# alphanewt_v1_8.net
KiCad netlist of a schematic drawn in EAGLE
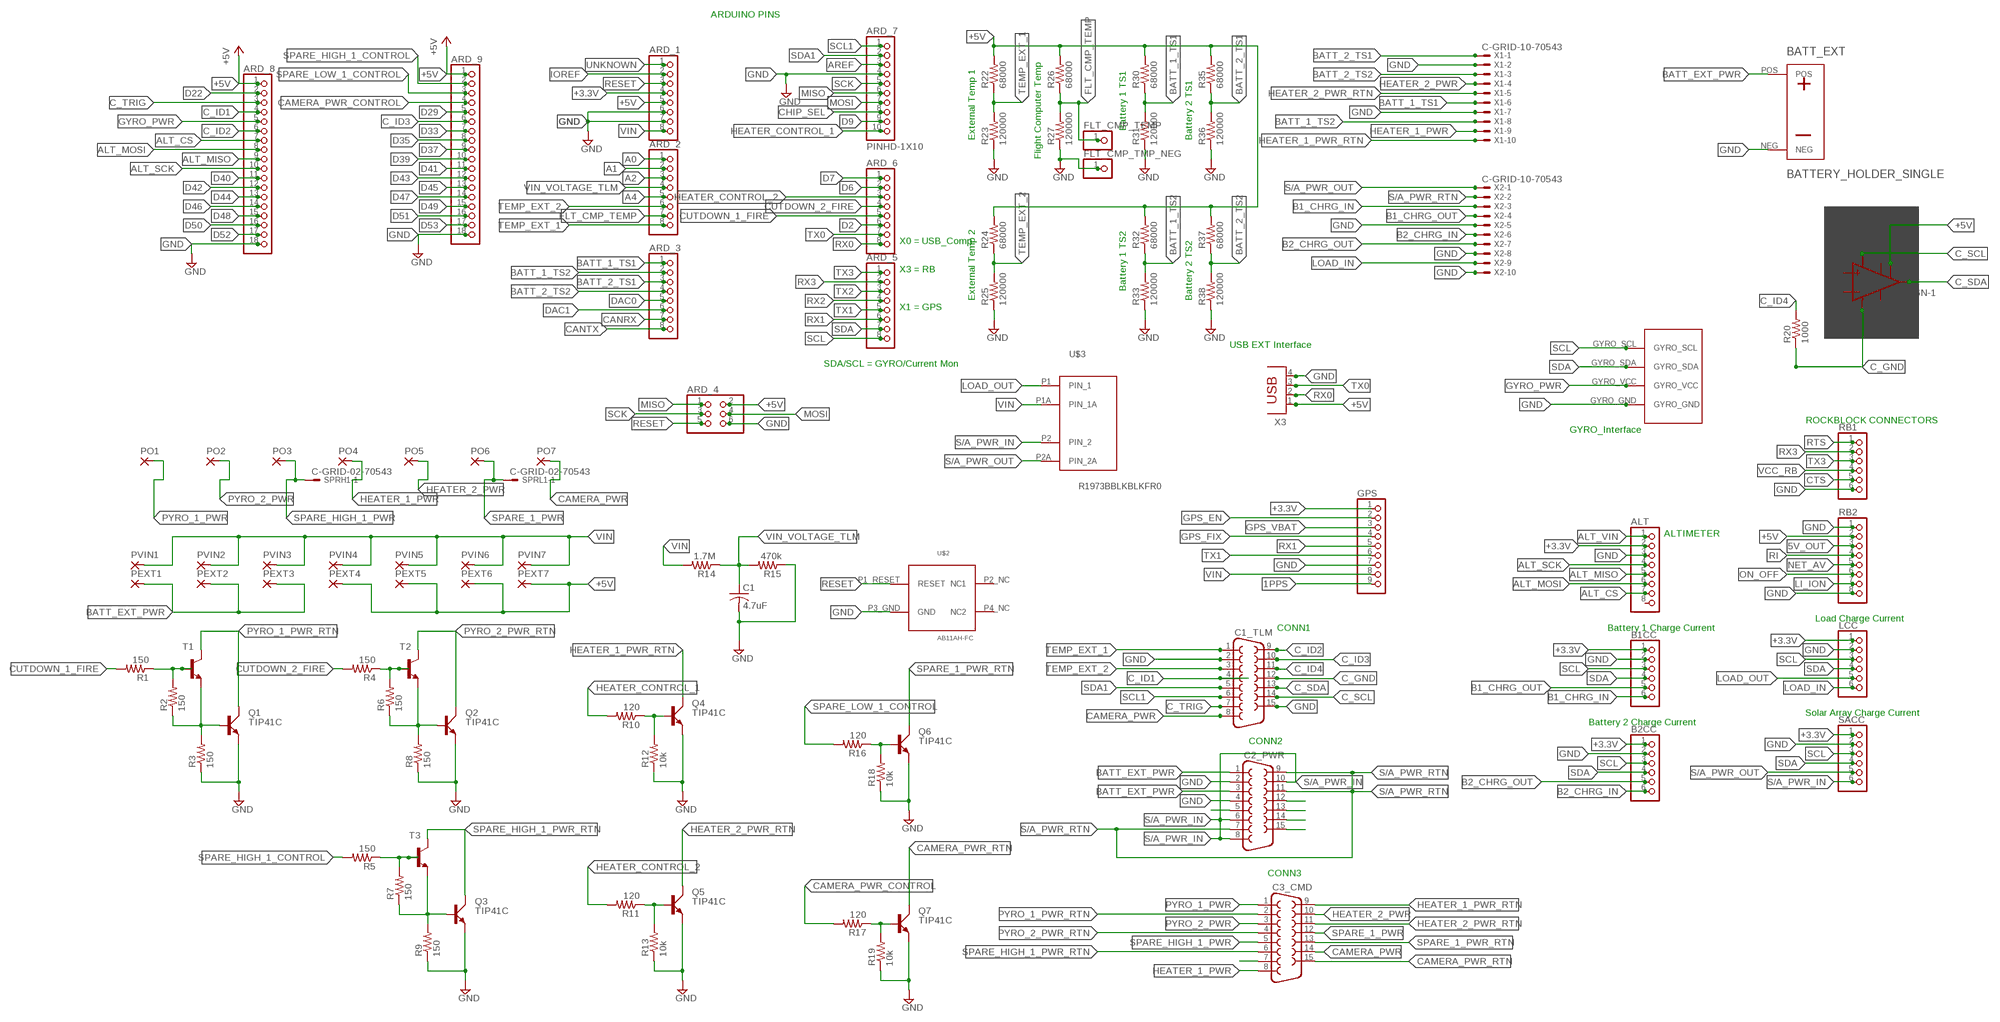
[diagram p0: schematic, sheet 1]

(export (version "E")
  (design (tool "Eeschema 10.0.6"))
  (components
    (comp (ref "ALT")
      (value "PINHD-1X8BIG")
      (footprint "eagle-import:1X08-BIG")
      (libsource (lib "eagle-import") (part "PINHD-1X8BIG"))
    )
    (comp (ref "ARD_1")
      (value "PINHD-1X8BIG")
      (footprint "eagle-import:1X08-BIG")
      (libsource (lib "eagle-import") (part "PINHD-1X8BIG"))
    )
    (comp (ref "ARD_2")
      (value "PINHD-1X8BIG")
      (footprint "eagle-import:1X08-BIG")
      (libsource (lib "eagle-import") (part "PINHD-1X8BIG"))
    )
    (comp (ref "ARD_3")
      (value "PINHD-1X8BIG")
      (footprint "eagle-import:1X08-BIG")
      (libsource (lib "eagle-import") (part "PINHD-1X8BIG"))
    )
    (comp (ref "ARD_4")
      (value "PINHD-2X3")
      (footprint "eagle-import:2X03")
      (libsource (lib "eagle-import") (part "PINHD-2X3"))
    )
    (comp (ref "ARD_5")
      (value "PINHD-1X8BIG")
      (footprint "eagle-import:1X08-BIG")
      (libsource (lib "eagle-import") (part "PINHD-1X8BIG"))
    )
    (comp (ref "ARD_6")
      (value "PINHD-1X8BIG")
      (footprint "eagle-import:1X08-BIG")
      (libsource (lib "eagle-import") (part "PINHD-1X8BIG"))
    )
    (comp (ref "ARD_7")
      (value "PINHD-1X10")
      (footprint "eagle-import:1X10-BIG")
      (libsource (lib "eagle-import") (part "PINHD-1X10"))
    )
    (comp (ref "ARD_8")
      (value "PINHD-1X18-BIG")
      (footprint "eagle-import:1X18-BIG")
      (libsource (lib "eagle-import") (part "PINHD-1X18-BIG"))
    )
    (comp (ref "ARD_9")
      (value "PINHD-1X18-BIG")
      (footprint "eagle-import:1X18-BIG")
      (libsource (lib "eagle-import") (part "PINHD-1X18-BIG"))
    )
    (comp (ref "B1CC")
      (value "PINHD-1X6B")
      (footprint "eagle-import:1X06-BIG")
      (libsource (lib "eagle-import") (part "PINHD-1X6B"))
    )
    (comp (ref "B2CC")
      (value "PINHD-1X6B")
      (footprint "eagle-import:1X06-BIG")
      (libsource (lib "eagle-import") (part "PINHD-1X6B"))
    )
    (comp (ref "BATT_EXT")
      (value "BATTERY_HOLDER_SINGLE")
      (footprint "eagle-import:BATT_HOLDER_SINGLE")
      (libsource (lib "eagle-import") (part "BATTERY_HOLDER_SINGLE"))
    )
    (comp (ref "C1")
      (value "4.7uF")
      (footprint "eagle-import:C0805K")
      (fields (field (name "MPN") "C2012X6S1H475K125AC"))
      (libsource (lib "eagle-import") (part "C-USC0805K"))
    )
    (comp (ref "C1_TLM")
      (value "F15HP")
      (footprint "eagle-import:F15HP")
      (fields (field (name "MPN") "5504F1-15S-02A-03"))
      (libsource (lib "eagle-import") (part "F15HP"))
    )
    (comp (ref "C2_PWR")
      (value "F15HP")
      (footprint "eagle-import:F15HP")
      (fields (field (name "MPN") "5504F1-15S-02A-03"))
      (libsource (lib "eagle-import") (part "F15HP"))
    )
    (comp (ref "C3_CMD")
      (value "F15HP")
      (footprint "eagle-import:F15HP")
      (fields (field (name "MPN") "5504F1-15S-02A-03"))
      (libsource (lib "eagle-import") (part "F15HP"))
    )
    (comp (ref "FLT_CMP_TEMP")
      (value "PINHD-1X1")
      (footprint "eagle-import:1X01")
      (libsource (lib "eagle-import") (part "PINHD-1X1"))
    )
    (comp (ref "FLT_CMP_TMP_NEG")
      (value "PINHD-1X1")
      (footprint "eagle-import:1X01")
      (libsource (lib "eagle-import") (part "PINHD-1X1"))
    )
    (comp (ref "GPS")
      (value "PINHD-1X9")
      (footprint "eagle-import:1X09-BIG")
      (libsource (lib "eagle-import") (part "PINHD-1X9"))
    )
    (comp (ref "IC1")
      (value "LM386N-1")
      (footprint "eagle-import:DIL08")
      (libsource (lib "eagle-import") (part "LM386?-N1"))
    )
    (comp (ref "LCC")
      (value "PINHD-1X6B")
      (footprint "eagle-import:1X06-BIG")
      (libsource (lib "eagle-import") (part "PINHD-1X6B"))
    )
    (comp (ref "PEXT1")
      (value "SMD2")
      (footprint "eagle-import:SMD1,27-2,54")
      (libsource (lib "eagle-import") (part "SMD2"))
    )
    (comp (ref "PEXT2")
      (value "SMD2")
      (footprint "eagle-import:SMD1,27-2,54")
      (libsource (lib "eagle-import") (part "SMD2"))
    )
    (comp (ref "PEXT3")
      (value "SMD2")
      (footprint "eagle-import:SMD1,27-2,54")
      (libsource (lib "eagle-import") (part "SMD2"))
    )
    (comp (ref "PEXT4")
      (value "SMD2")
      (footprint "eagle-import:SMD1,27-2,54")
      (libsource (lib "eagle-import") (part "SMD2"))
    )
    (comp (ref "PEXT5")
      (value "SMD2")
      (footprint "eagle-import:SMD1,27-2,54")
      (libsource (lib "eagle-import") (part "SMD2"))
    )
    (comp (ref "PEXT6")
      (value "SMD2")
      (footprint "eagle-import:SMD1,27-2,54")
      (libsource (lib "eagle-import") (part "SMD2"))
    )
    (comp (ref "PEXT7")
      (value "SMD2")
      (footprint "eagle-import:SMD1,27-2,54")
      (libsource (lib "eagle-import") (part "SMD2"))
    )
    (comp (ref "PO1")
      (value "SMD2")
      (footprint "eagle-import:SMD1,27-2,54")
      (libsource (lib "eagle-import") (part "SMD2"))
    )
    (comp (ref "PO2")
      (value "SMD2")
      (footprint "eagle-import:SMD1,27-2,54")
      (libsource (lib "eagle-import") (part "SMD2"))
    )
    (comp (ref "PO3")
      (value "SMD2")
      (footprint "eagle-import:SMD1,27-2,54")
      (libsource (lib "eagle-import") (part "SMD2"))
    )
    (comp (ref "PO4")
      (value "SMD2")
      (footprint "eagle-import:SMD1,27-2,54")
      (libsource (lib "eagle-import") (part "SMD2"))
    )
    (comp (ref "PO5")
      (value "SMD2")
      (footprint "eagle-import:SMD1,27-2,54")
      (libsource (lib "eagle-import") (part "SMD2"))
    )
    (comp (ref "PO6")
      (value "SMD2")
      (footprint "eagle-import:SMD1,27-2,54")
      (libsource (lib "eagle-import") (part "SMD2"))
    )
    (comp (ref "PO7")
      (value "SMD2")
      (footprint "eagle-import:SMD1,27-2,54")
      (libsource (lib "eagle-import") (part "SMD2"))
    )
    (comp (ref "PVIN1")
      (value "SMD2")
      (footprint "eagle-import:SMD1,27-2,54")
      (libsource (lib "eagle-import") (part "SMD2"))
    )
    (comp (ref "PVIN2")
      (value "SMD2")
      (footprint "eagle-import:SMD1,27-2,54")
      (libsource (lib "eagle-import") (part "SMD2"))
    )
    (comp (ref "PVIN3")
      (value "SMD2")
      (footprint "eagle-import:SMD1,27-2,54")
      (libsource (lib "eagle-import") (part "SMD2"))
    )
    (comp (ref "PVIN4")
      (value "SMD2")
      (footprint "eagle-import:SMD1,27-2,54")
      (libsource (lib "eagle-import") (part "SMD2"))
    )
    (comp (ref "PVIN5")
      (value "SMD2")
      (footprint "eagle-import:SMD1,27-2,54")
      (libsource (lib "eagle-import") (part "SMD2"))
    )
    (comp (ref "PVIN6")
      (value "SMD2")
      (footprint "eagle-import:SMD1,27-2,54")
      (libsource (lib "eagle-import") (part "SMD2"))
    )
    (comp (ref "PVIN7")
      (value "SMD2")
      (footprint "eagle-import:SMD1,27-2,54")
      (libsource (lib "eagle-import") (part "SMD2"))
    )
    (comp (ref "Q1")
      (value "TIP41C")
      (footprint "eagle-import:TO220AV")
      (fields (field (name "MF") "FAIRCHILD SEMICONDUCTOR"))
      (libsource (lib "eagle-import") (part "TIP41C"))
    )
    (comp (ref "Q2")
      (value "TIP41C")
      (footprint "eagle-import:TO220AV")
      (fields (field (name "MF") "FAIRCHILD SEMICONDUCTOR"))
      (libsource (lib "eagle-import") (part "TIP41C"))
    )
    (comp (ref "Q3")
      (value "TIP41C")
      (footprint "eagle-import:TO220AV")
      (fields (field (name "MF") "FAIRCHILD SEMICONDUCTOR"))
      (libsource (lib "eagle-import") (part "TIP41C"))
    )
    (comp (ref "Q4")
      (value "TIP41C")
      (footprint "eagle-import:TO220AV")
      (fields (field (name "MF") "FAIRCHILD SEMICONDUCTOR"))
      (libsource (lib "eagle-import") (part "TIP41C"))
    )
    (comp (ref "Q5")
      (value "TIP41C")
      (footprint "eagle-import:TO220AV")
      (fields (field (name "MF") "FAIRCHILD SEMICONDUCTOR"))
      (libsource (lib "eagle-import") (part "TIP41C"))
    )
    (comp (ref "Q6")
      (value "TIP41C")
      (footprint "eagle-import:TO220AV")
      (fields (field (name "MF") "FAIRCHILD SEMICONDUCTOR"))
      (libsource (lib "eagle-import") (part "TIP41C"))
    )
    (comp (ref "Q7")
      (value "TIP41C")
      (footprint "eagle-import:TO220AV")
      (fields (field (name "MF") "FAIRCHILD SEMICONDUCTOR"))
      (libsource (lib "eagle-import") (part "TIP41C"))
    )
    (comp (ref "R1")
      (value "150")
      (footprint "eagle-import:R0805")
      (fields (field (name "MF") "VISHAY/DALE") (field (name "MPN") "CRCW120633R2FKEA"))
      (libsource (lib "eagle-import") (part "R-US_R0805"))
    )
    (comp (ref "R2")
      (value "150")
      (footprint "eagle-import:R0805")
      (fields (field (name "MF") "VISHAY/DALE") (field (name "MPN") "CRCW120633R2FKEA"))
      (libsource (lib "eagle-import") (part "R-US_R0805"))
    )
    (comp (ref "R3")
      (value "150")
      (footprint "eagle-import:R0805")
      (fields (field (name "MF") "VISHAY/DALE") (field (name "MPN") "CRCW120633R2FKEA"))
      (libsource (lib "eagle-import") (part "R-US_R0805"))
    )
    (comp (ref "R4")
      (value "150")
      (footprint "eagle-import:R0805")
      (fields (field (name "MF") "VISHAY/DALE") (field (name "MPN") "CRCW120633R2FKEA"))
      (libsource (lib "eagle-import") (part "R-US_R0805"))
    )
    (comp (ref "R5")
      (value "150")
      (footprint "eagle-import:R0805")
      (fields (field (name "MF") "VISHAY/DALE") (field (name "MPN") "CRCW120633R2FKEA"))
      (libsource (lib "eagle-import") (part "R-US_R0805"))
    )
    (comp (ref "R6")
      (value "150")
      (footprint "eagle-import:R0805")
      (fields (field (name "MF") "VISHAY/DALE") (field (name "MPN") "CRCW120633R2FKEA"))
      (libsource (lib "eagle-import") (part "R-US_R0805"))
    )
    (comp (ref "R7")
      (value "150")
      (footprint "eagle-import:R0805")
      (fields (field (name "MF") "VISHAY/DALE") (field (name "MPN") "CRCW120633R2FKEA"))
      (libsource (lib "eagle-import") (part "R-US_R0805"))
    )
    (comp (ref "R8")
      (value "150")
      (footprint "eagle-import:R0805")
      (fields (field (name "MF") "VISHAY/DALE") (field (name "MPN") "CRCW120633R2FKEA"))
      (libsource (lib "eagle-import") (part "R-US_R0805"))
    )
    (comp (ref "R9")
      (value "150")
      (footprint "eagle-import:R0805")
      (fields (field (name "MF") "VISHAY/DALE") (field (name "MPN") "CRCW120633R2FKEA"))
      (libsource (lib "eagle-import") (part "R-US_R0805"))
    )
    (comp (ref "R10")
      (value "120")
      (footprint "eagle-import:R0805")
      (fields (field (name "MF") "VISHAY/DALE") (field (name "MPN") "CRCW120633R2FKEA"))
      (libsource (lib "eagle-import") (part "R-US_R0805"))
    )
    (comp (ref "R11")
      (value "120")
      (footprint "eagle-import:R0805")
      (fields (field (name "MF") "VISHAY/DALE") (field (name "MPN") "CRCW120633R2FKEA"))
      (libsource (lib "eagle-import") (part "R-US_R0805"))
    )
    (comp (ref "R12")
      (value "10k")
      (footprint "eagle-import:R0805")
      (fields (field (name "MF") "VISHAY/DALE") (field (name "MPN") "CRCW120633R2FKEA"))
      (libsource (lib "eagle-import") (part "R-US_R0805"))
    )
    (comp (ref "R13")
      (value "10k")
      (footprint "eagle-import:R0805")
      (fields (field (name "MF") "VISHAY/DALE") (field (name "MPN") "CRCW120633R2FKEA"))
      (libsource (lib "eagle-import") (part "R-US_R0805"))
    )
    (comp (ref "R14")
      (value "1.7M")
      (footprint "eagle-import:R0805")
      (fields (field (name "MF") "VISHAY/DALE") (field (name "MPN") "CRCW120633R2FKEA"))
      (libsource (lib "eagle-import") (part "R-US_R0805"))
    )
    (comp (ref "R15")
      (value "470k")
      (footprint "eagle-import:R0805")
      (fields (field (name "MF") "VISHAY/DALE") (field (name "MPN") "CRCW120633R2FKEA"))
      (libsource (lib "eagle-import") (part "R-US_R0805"))
    )
    (comp (ref "R16")
      (value "120")
      (footprint "eagle-import:R0805")
      (fields (field (name "MF") "VISHAY/DALE") (field (name "MPN") "CRCW120633R2FKEA"))
      (libsource (lib "eagle-import") (part "R-US_R0805"))
    )
    (comp (ref "R17")
      (value "120")
      (footprint "eagle-import:R0805")
      (fields (field (name "MF") "VISHAY/DALE") (field (name "MPN") "CRCW120633R2FKEA"))
      (libsource (lib "eagle-import") (part "R-US_R0805"))
    )
    (comp (ref "R18")
      (value "10k")
      (footprint "eagle-import:R0805")
      (fields (field (name "MF") "VISHAY/DALE") (field (name "MPN") "CRCW120633R2FKEA"))
      (libsource (lib "eagle-import") (part "R-US_R0805"))
    )
    (comp (ref "R19")
      (value "10k")
      (footprint "eagle-import:R0805")
      (fields (field (name "MF") "VISHAY/DALE") (field (name "MPN") "CRCW120633R2FKEA"))
      (libsource (lib "eagle-import") (part "R-US_R0805"))
    )
    (comp (ref "R20")
      (value "1000")
      (footprint "eagle-import:R0805")
      (fields (field (name "MF") "VISHAY/DALE") (field (name "MPN") "CRCW120633R2FKEA"))
      (libsource (lib "eagle-import") (part "R-US_R0805"))
    )
    (comp (ref "R22")
      (value "68000")
      (footprint "eagle-import:R0805")
      (fields (field (name "MF") "VISHAY/DALE") (field (name "MPN") "CRCW120633R2FKEA"))
      (libsource (lib "eagle-import") (part "R-US_R0805"))
    )
    (comp (ref "R23")
      (value "120000")
      (footprint "eagle-import:R0805")
      (fields (field (name "MF") "VISHAY/DALE") (field (name "MPN") "CRCW120633R2FKEA"))
      (libsource (lib "eagle-import") (part "R-US_R0805"))
    )
    (comp (ref "R24")
      (value "68000")
      (footprint "eagle-import:R0805")
      (fields (field (name "MF") "VISHAY/DALE") (field (name "MPN") "CRCW120633R2FKEA"))
      (libsource (lib "eagle-import") (part "R-US_R0805"))
    )
    (comp (ref "R25")
      (value "120000")
      (footprint "eagle-import:R0805")
      (fields (field (name "MF") "VISHAY/DALE") (field (name "MPN") "CRCW120633R2FKEA"))
      (libsource (lib "eagle-import") (part "R-US_R0805"))
    )
    (comp (ref "R26")
      (value "68000")
      (footprint "eagle-import:R0805")
      (fields (field (name "MF") "VISHAY/DALE") (field (name "MPN") "CRCW120633R2FKEA"))
      (libsource (lib "eagle-import") (part "R-US_R0805"))
    )
    (comp (ref "R27")
      (value "120000")
      (footprint "eagle-import:R0805")
      (fields (field (name "MF") "VISHAY/DALE") (field (name "MPN") "CRCW120633R2FKEA"))
      (libsource (lib "eagle-import") (part "R-US_R0805"))
    )
    (comp (ref "R30")
      (value "68000")
      (footprint "eagle-import:R0805")
      (fields (field (name "MF") "VISHAY/DALE") (field (name "MPN") "CRCW120633R2FKEA"))
      (libsource (lib "eagle-import") (part "R-US_R0805"))
    )
    (comp (ref "R31")
      (value "120000")
      (footprint "eagle-import:R0805")
      (fields (field (name "MF") "VISHAY/DALE") (field (name "MPN") "CRCW120633R2FKEA"))
      (libsource (lib "eagle-import") (part "R-US_R0805"))
    )
    (comp (ref "R32")
      (value "68000")
      (footprint "eagle-import:R0805")
      (fields (field (name "MF") "VISHAY/DALE") (field (name "MPN") "CRCW120633R2FKEA"))
      (libsource (lib "eagle-import") (part "R-US_R0805"))
    )
    (comp (ref "R33")
      (value "120000")
      (footprint "eagle-import:R0805")
      (fields (field (name "MF") "VISHAY/DALE") (field (name "MPN") "CRCW120633R2FKEA"))
      (libsource (lib "eagle-import") (part "R-US_R0805"))
    )
    (comp (ref "R35")
      (value "68000")
      (footprint "eagle-import:R0805")
      (fields (field (name "MF") "VISHAY/DALE") (field (name "MPN") "CRCW120633R2FKEA"))
      (libsource (lib "eagle-import") (part "R-US_R0805"))
    )
    (comp (ref "R36")
      (value "120000")
      (footprint "eagle-import:R0805")
      (fields (field (name "MF") "VISHAY/DALE") (field (name "MPN") "CRCW120633R2FKEA"))
      (libsource (lib "eagle-import") (part "R-US_R0805"))
    )
    (comp (ref "R37")
      (value "68000")
      (footprint "eagle-import:R0805")
      (fields (field (name "MF") "VISHAY/DALE") (field (name "MPN") "CRCW120633R2FKEA"))
      (libsource (lib "eagle-import") (part "R-US_R0805"))
    )
    (comp (ref "R38")
      (value "120000")
      (footprint "eagle-import:R0805")
      (fields (field (name "MF") "VISHAY/DALE") (field (name "MPN") "CRCW120633R2FKEA"))
      (libsource (lib "eagle-import") (part "R-US_R0805"))
    )
    (comp (ref "RB1")
      (value "PINHD-1X6CB")
      (footprint "eagle-import:1X06-CLEANBIG")
      (libsource (lib "eagle-import") (part "PINHD-1X6CB"))
    )
    (comp (ref "RB2")
      (value "PINHD-1X8BIG")
      (footprint "eagle-import:1X08-BIG")
      (libsource (lib "eagle-import") (part "PINHD-1X8BIG"))
    )
    (comp (ref "SACC")
      (value "PINHD-1X6B")
      (footprint "eagle-import:1X06-BIG")
      (libsource (lib "eagle-import") (part "PINHD-1X6B"))
    )
    (comp (ref "SPRH1")
      (value "C-GRID-02-70543")
      (footprint "eagle-import:70543-02")
      (fields
        (field (name "MF") "MOLEX")
        (field (name "MPN") "70543-0001")
        (field (name "OC_NEWARK") "59H2645")
      )
      (libsource (lib "eagle-import") (part "C-GRID-02-70543"))
    )
    (comp (ref "SPRL1")
      (value "C-GRID-02-70543")
      (footprint "eagle-import:70543-02")
      (fields
        (field (name "MF") "MOLEX")
        (field (name "MPN") "70543-0001")
        (field (name "OC_NEWARK") "59H2645")
      )
      (libsource (lib "eagle-import") (part "C-GRID-02-70543"))
    )
    (comp (ref "T1")
      (value "2N3904")
      (footprint "eagle-import:TO92")
      (fields (field (name "MF") "NTE ELECTRONICS"))
      (libsource (lib "eagle-import") (part "2N3904"))
    )
    (comp (ref "T2")
      (value "2N3904")
      (footprint "eagle-import:TO92")
      (fields (field (name "MF") "NTE ELECTRONICS"))
      (libsource (lib "eagle-import") (part "2N3904"))
    )
    (comp (ref "T3")
      (value "2N3904")
      (footprint "eagle-import:TO92")
      (fields (field (name "MF") "NTE ELECTRONICS"))
      (libsource (lib "eagle-import") (part "2N3904"))
    )
    (comp (ref "U$2")
      (value "AB11AH-FC")
      (footprint "eagle-import:AB11AH-FC")
      (libsource (lib "eagle-import") (part "AB11AH-FC"))
    )
    (comp (ref "U$3")
      (value "R1973BBLKBLKFR0")
      (footprint "eagle-import:R1973BBLKBLKFR0")
      (libsource (lib "eagle-import") (part "R1973BBLKBLKFR0"))
    )
    (comp (ref "U$4")
      (value "GYRO_MPU9250_FOOTPRINT")
      (footprint "eagle-import:MPU9250_FOOTPRINT")
      (libsource (lib "eagle-import") (part "GYRO_MPU9250_FOOTPRINT"))
    )
    (comp (ref "X1")
      (value "C-GRID-10-70543")
      (footprint "eagle-import:70543-10")
      (libsource (lib "eagle-import") (part "C-GRID-10-70543"))
    )
    (comp (ref "X2")
      (value "C-GRID-10-70543")
      (footprint "eagle-import:70543-10")
      (libsource (lib "eagle-import") (part "C-GRID-10-70543"))
    )
    (comp (ref "X3")
      (value "PN87520")
      (footprint "eagle-import:PN87520")
      (libsource (lib "eagle-import") (part "PN87520"))
    )
  )
  (nets
    (net (code "1") (name "+3.3V") (class "Default")
      (node (ref "ALT") (pin "2") (pinfunction "2_2") (pintype "passive"))
      (node (ref "ARD_1") (pin "4") (pinfunction "4_4") (pintype "passive"))
      (node (ref "B1CC") (pin "1") (pinfunction "1_1") (pintype "passive"))
      (node (ref "B2CC") (pin "1") (pinfunction "1_1") (pintype "passive"))
      (node (ref "GPS") (pin "1") (pinfunction "1_1") (pintype "passive"))
      (node (ref "LCC") (pin "1") (pinfunction "1_1") (pintype "passive"))
      (node (ref "SACC") (pin "1") (pinfunction "1_1") (pintype "passive"))
    )
    (net (code "2") (name "+5V") (class "Default")
      (node (ref "ARD_1") (pin "5") (pinfunction "5_5") (pintype "passive"))
      (node (ref "ARD_4") (pin "2") (pinfunction "2_2") (pintype "passive"))
      (node (ref "ARD_8") (pin "1") (pinfunction "1_1") (pintype "passive"))
      (node (ref "ARD_9") (pin "1") (pinfunction "1_1") (pintype "passive"))
      (node (ref "IC1") (pin "8") (pinfunction "GAIN_8") (pintype "passive"))
      (node (ref "PEXT4") (pin "1") (pinfunction "P_1") (pintype "passive"))
      (node (ref "PEXT5") (pin "1") (pinfunction "P_1") (pintype "passive"))
      (node (ref "PEXT6") (pin "1") (pinfunction "P_1") (pintype "passive"))
      (node (ref "PEXT7") (pin "1") (pinfunction "P_1") (pintype "passive"))
      (node (ref "R22") (pin "2") (pinfunction "2_2") (pintype "passive"))
      (node (ref "R24") (pin "2") (pinfunction "2_2") (pintype "passive"))
      (node (ref "R26") (pin "2") (pinfunction "2_2") (pintype "passive"))
      (node (ref "R30") (pin "2") (pinfunction "2_2") (pintype "passive"))
      (node (ref "R32") (pin "2") (pinfunction "2_2") (pintype "passive"))
      (node (ref "R35") (pin "2") (pinfunction "2_2") (pintype "passive"))
      (node (ref "R37") (pin "2") (pinfunction "2_2") (pintype "passive"))
      (node (ref "RB2") (pin "2") (pinfunction "2_2") (pintype "passive"))
      (node (ref "X3") (pin "1") (pinfunction "1_1") (pintype "passive"))
    )
    (net (code "3") (name "1PPS") (class "Default")
      (node (ref "GPS") (pin "9") (pinfunction "9_9") (pintype "passive"))
    )
    (net (code "4") (name "5V_OUT") (class "Default")
      (node (ref "RB2") (pin "3") (pinfunction "3_3") (pintype "passive"))
    )
    (net (code "5") (name "A0") (class "Default")
      (node (ref "ARD_2") (pin "1") (pinfunction "1_1") (pintype "passive"))
    )
    (net (code "6") (name "A1") (class "Default")
      (node (ref "ARD_2") (pin "2") (pinfunction "2_2") (pintype "passive"))
    )
    (net (code "7") (name "A2") (class "Default")
      (node (ref "ARD_2") (pin "3") (pinfunction "3_3") (pintype "passive"))
    )
    (net (code "8") (name "A4") (class "Default")
      (node (ref "ARD_2") (pin "5") (pinfunction "5_5") (pintype "passive"))
    )
    (net (code "9") (name "ALT_CS") (class "Default")
      (node (ref "ALT") (pin "7") (pinfunction "7_7") (pintype "passive"))
      (node (ref "ARD_8") (pin "7") (pinfunction "7_7") (pintype "passive"))
    )
    (net (code "10") (name "ALT_MISO") (class "Default")
      (node (ref "ALT") (pin "5") (pinfunction "5_5") (pintype "passive"))
      (node (ref "ARD_8") (pin "9") (pinfunction "9_9") (pintype "passive"))
    )
    (net (code "11") (name "ALT_MOSI") (class "Default")
      (node (ref "ALT") (pin "6") (pinfunction "6_6") (pintype "passive"))
      (node (ref "ARD_8") (pin "8") (pinfunction "8_8") (pintype "passive"))
    )
    (net (code "12") (name "ALT_SCK") (class "Default")
      (node (ref "ALT") (pin "4") (pinfunction "4_4") (pintype "passive"))
      (node (ref "ARD_8") (pin "10") (pinfunction "10_10") (pintype "passive"))
    )
    (net (code "13") (name "ALT_VIN") (class "Default")
      (node (ref "ALT") (pin "1") (pinfunction "1_1") (pintype "passive"))
    )
    (net (code "14") (name "AREF") (class "Default")
      (node (ref "ARD_7") (pin "3") (pinfunction "3_3") (pintype "passive"))
    )
    (net (code "15") (name "B1_CHRG_IN") (class "Default")
      (node (ref "B1CC") (pin "6") (pinfunction "6_6") (pintype "passive"))
      (node (ref "X2") (pin "3") (pinfunction "S_3") (pintype "passive"))
    )
    (net (code "16") (name "B1_CHRG_OUT") (class "Default")
      (node (ref "B1CC") (pin "5") (pinfunction "5_5") (pintype "passive"))
      (node (ref "X2") (pin "4") (pinfunction "S_4") (pintype "passive"))
    )
    (net (code "17") (name "B2_CHRG_IN") (class "Default")
      (node (ref "B2CC") (pin "6") (pinfunction "6_6") (pintype "passive"))
      (node (ref "X2") (pin "6") (pinfunction "S_6") (pintype "passive"))
    )
    (net (code "18") (name "B2_CHRG_OUT") (class "Default")
      (node (ref "B2CC") (pin "5") (pinfunction "5_5") (pintype "passive"))
      (node (ref "X2") (pin "7") (pinfunction "S_7") (pintype "passive"))
    )
    (net (code "19") (name "BATT_1_TS1") (class "Default")
      (node (ref "ARD_3") (pin "1") (pinfunction "1_1") (pintype "passive"))
      (node (ref "R30") (pin "1") (pinfunction "1_1") (pintype "passive"))
      (node (ref "R31") (pin "2") (pinfunction "2_2") (pintype "passive"))
      (node (ref "X1") (pin "6") (pinfunction "S_6") (pintype "passive"))
    )
    (net (code "20") (name "BATT_1_TS2") (class "Default")
      (node (ref "ARD_3") (pin "2") (pinfunction "2_2") (pintype "passive"))
      (node (ref "R32") (pin "1") (pinfunction "1_1") (pintype "passive"))
      (node (ref "R33") (pin "2") (pinfunction "2_2") (pintype "passive"))
      (node (ref "X1") (pin "8") (pinfunction "S_8") (pintype "passive"))
    )
    (net (code "21") (name "BATT_2_TS1") (class "Default")
      (node (ref "ARD_3") (pin "3") (pinfunction "3_3") (pintype "passive"))
      (node (ref "R35") (pin "1") (pinfunction "1_1") (pintype "passive"))
      (node (ref "R36") (pin "2") (pinfunction "2_2") (pintype "passive"))
      (node (ref "X1") (pin "1") (pinfunction "S_1") (pintype "passive"))
    )
    (net (code "22") (name "BATT_2_TS2") (class "Default")
      (node (ref "ARD_3") (pin "4") (pinfunction "4_4") (pintype "passive"))
      (node (ref "R37") (pin "1") (pinfunction "1_1") (pintype "passive"))
      (node (ref "R38") (pin "2") (pinfunction "2_2") (pintype "passive"))
      (node (ref "X1") (pin "3") (pinfunction "S_3") (pintype "passive"))
    )
    (net (code "23") (name "BATT_EXT_PWR") (class "Default")
      (node (ref "BATT_EXT") (pin "POS") (pinfunction "POS_POS") (pintype "bidirectional"))
      (node (ref "C2_PWR") (pin "1") (pinfunction "1_1") (pintype "passive"))
      (node (ref "C2_PWR") (pin "3") (pinfunction "3_3") (pintype "passive"))
      (node (ref "PEXT1") (pin "1") (pinfunction "P_1") (pintype "passive"))
      (node (ref "PEXT2") (pin "1") (pinfunction "P_1") (pintype "passive"))
      (node (ref "PEXT3") (pin "1") (pinfunction "P_1") (pintype "passive"))
    )
    (net (code "24") (name "CAMERA_PWR") (class "Default")
      (node (ref "C1_TLM") (pin "8") (pinfunction "8_8") (pintype "passive"))
      (node (ref "C3_CMD") (pin "14") (pinfunction "14_14") (pintype "passive"))
      (node (ref "PO7") (pin "1") (pinfunction "P_1") (pintype "passive"))
    )
    (net (code "25") (name "CAMERA_PWR_CONTROL") (class "Default")
      (node (ref "ARD_9") (pin "4") (pinfunction "4_4") (pintype "passive"))
      (node (ref "R17") (pin "2") (pinfunction "2_2") (pintype "passive"))
    )
    (net (code "26") (name "CAMERA_PWR_RTN") (class "Default")
      (node (ref "C3_CMD") (pin "15") (pinfunction "15_15") (pintype "passive"))
      (node (ref "Q7") (pin "C") (pinfunction "C_C") (pintype "passive"))
    )
    (net (code "27") (name "CANRX") (class "Default")
      (node (ref "ARD_3") (pin "7") (pinfunction "7_7") (pintype "passive"))
    )
    (net (code "28") (name "CANTX") (class "Default")
      (node (ref "ARD_3") (pin "8") (pinfunction "8_8") (pintype "passive"))
    )
    (net (code "29") (name "CHIP_SEL") (class "Default")
      (node (ref "ARD_7") (pin "8") (pinfunction "8_8") (pintype "passive"))
    )
    (net (code "30") (name "CTS") (class "Default")
      (node (ref "RB1") (pin "5") (pinfunction "5_5") (pintype "passive"))
    )
    (net (code "31") (name "CUTDOWN_1_FIRE") (class "Default")
      (node (ref "ARD_6") (pin "5") (pinfunction "5_5") (pintype "passive"))
      (node (ref "R1") (pin "2") (pinfunction "2_2") (pintype "passive"))
    )
    (net (code "32") (name "CUTDOWN_2_FIRE") (class "Default")
      (node (ref "ARD_6") (pin "4") (pinfunction "4_4") (pintype "passive"))
      (node (ref "R4") (pin "2") (pinfunction "2_2") (pintype "passive"))
    )
    (net (code "33") (name "C_GND") (class "Default")
      (node (ref "C1_TLM") (pin "12") (pinfunction "12_12") (pintype "passive"))
      (node (ref "IC1") (pin "4") (pinfunction "GND_4") (pintype "power_in"))
      (node (ref "R20") (pin "1") (pinfunction "1_1") (pintype "passive"))
    )
    (net (code "34") (name "C_ID1") (class "Default")
      (node (ref "ARD_8") (pin "4") (pinfunction "4_4") (pintype "passive"))
      (node (ref "C1_TLM") (pin "4") (pinfunction "4_4") (pintype "passive"))
    )
    (net (code "35") (name "C_ID2") (class "Default")
      (node (ref "ARD_8") (pin "6") (pinfunction "6_6") (pintype "passive"))
      (node (ref "C1_TLM") (pin "9") (pinfunction "9_9") (pintype "passive"))
    )
    (net (code "36") (name "C_ID3") (class "Default")
      (node (ref "ARD_9") (pin "6") (pinfunction "6_6") (pintype "passive"))
      (node (ref "C1_TLM") (pin "10") (pinfunction "10_10") (pintype "passive"))
    )
    (net (code "37") (name "C_ID4") (class "Default")
      (node (ref "C1_TLM") (pin "11") (pinfunction "11_11") (pintype "passive"))
      (node (ref "R20") (pin "2") (pinfunction "2_2") (pintype "passive"))
    )
    (net (code "38") (name "C_SCL") (class "Default")
      (node (ref "C1_TLM") (pin "14") (pinfunction "14_14") (pintype "passive"))
      (node (ref "IC1") (pin "6") (pinfunction "VS_6") (pintype "power_in"))
    )
    (net (code "39") (name "C_SDA") (class "Default")
      (node (ref "C1_TLM") (pin "13") (pinfunction "13_13") (pintype "passive"))
      (node (ref "IC1") (pin "5") (pinfunction "OUT_5") (pintype "output"))
    )
    (net (code "40") (name "C_TRIG") (class "Default")
      (node (ref "ARD_8") (pin "3") (pinfunction "3_3") (pintype "passive"))
      (node (ref "C1_TLM") (pin "7") (pinfunction "7_7") (pintype "passive"))
    )
    (net (code "41") (name "D2") (class "Default")
      (node (ref "ARD_6") (pin "6") (pinfunction "6_6") (pintype "passive"))
    )
    (net (code "42") (name "D6") (class "Default")
      (node (ref "ARD_6") (pin "2") (pinfunction "2_2") (pintype "passive"))
    )
    (net (code "43") (name "D7") (class "Default")
      (node (ref "ARD_6") (pin "1") (pinfunction "1_1") (pintype "passive"))
    )
    (net (code "44") (name "D9") (class "Default")
      (node (ref "ARD_7") (pin "9") (pinfunction "9_9") (pintype "passive"))
    )
    (net (code "45") (name "D22") (class "Default")
      (node (ref "ARD_8") (pin "2") (pinfunction "2_2") (pintype "passive"))
    )
    (net (code "46") (name "D29") (class "Default")
      (node (ref "ARD_9") (pin "5") (pinfunction "5_5") (pintype "passive"))
    )
    (net (code "47") (name "D33") (class "Default")
      (node (ref "ARD_9") (pin "7") (pinfunction "7_7") (pintype "passive"))
    )
    (net (code "48") (name "D35") (class "Default")
      (node (ref "ARD_9") (pin "8") (pinfunction "8_8") (pintype "passive"))
    )
    (net (code "49") (name "D37") (class "Default")
      (node (ref "ARD_9") (pin "9") (pinfunction "9_9") (pintype "passive"))
    )
    (net (code "50") (name "D39") (class "Default")
      (node (ref "ARD_9") (pin "10") (pinfunction "10_10") (pintype "passive"))
    )
    (net (code "51") (name "D40") (class "Default")
      (node (ref "ARD_8") (pin "11") (pinfunction "11_11") (pintype "passive"))
    )
    (net (code "52") (name "D41") (class "Default")
      (node (ref "ARD_9") (pin "11") (pinfunction "11_11") (pintype "passive"))
    )
    (net (code "53") (name "D42") (class "Default")
      (node (ref "ARD_8") (pin "12") (pinfunction "12_12") (pintype "passive"))
    )
    (net (code "54") (name "D43") (class "Default")
      (node (ref "ARD_9") (pin "12") (pinfunction "12_12") (pintype "passive"))
    )
    (net (code "55") (name "D44") (class "Default")
      (node (ref "ARD_8") (pin "13") (pinfunction "13_13") (pintype "passive"))
    )
    (net (code "56") (name "D45") (class "Default")
      (node (ref "ARD_9") (pin "13") (pinfunction "13_13") (pintype "passive"))
    )
    (net (code "57") (name "D46") (class "Default")
      (node (ref "ARD_8") (pin "14") (pinfunction "14_14") (pintype "passive"))
    )
    (net (code "58") (name "D47") (class "Default")
      (node (ref "ARD_9") (pin "14") (pinfunction "14_14") (pintype "passive"))
    )
    (net (code "59") (name "D48") (class "Default")
      (node (ref "ARD_8") (pin "15") (pinfunction "15_15") (pintype "passive"))
    )
    (net (code "60") (name "D49") (class "Default")
      (node (ref "ARD_9") (pin "15") (pinfunction "15_15") (pintype "passive"))
    )
    (net (code "61") (name "D50") (class "Default")
      (node (ref "ARD_8") (pin "16") (pinfunction "16_16") (pintype "passive"))
    )
    (net (code "62") (name "D51") (class "Default")
      (node (ref "ARD_9") (pin "16") (pinfunction "16_16") (pintype "passive"))
    )
    (net (code "63") (name "D52") (class "Default")
      (node (ref "ARD_8") (pin "17") (pinfunction "17_17") (pintype "passive"))
    )
    (net (code "64") (name "D53") (class "Default")
      (node (ref "ARD_9") (pin "17") (pinfunction "17_17") (pintype "passive"))
    )
    (net (code "65") (name "DAC0") (class "Default")
      (node (ref "ARD_3") (pin "5") (pinfunction "5_5") (pintype "passive"))
    )
    (net (code "66") (name "DAC1") (class "Default")
      (node (ref "ARD_3") (pin "6") (pinfunction "6_6") (pintype "passive"))
    )
    (net (code "67") (name "FLT_CMP_TEMP") (class "Default")
      (node (ref "ARD_2") (pin "7") (pinfunction "7_7") (pintype "passive"))
      (node (ref "FLT_CMP_TEMP") (pin "1") (pinfunction "1_1") (pintype "passive"))
      (node (ref "R26") (pin "1") (pinfunction "1_1") (pintype "passive"))
      (node (ref "R27") (pin "2") (pinfunction "2_2") (pintype "passive"))
    )
    (net (code "68") (name "GND") (class "Default")
      (node (ref "ALT") (pin "3") (pinfunction "3_3") (pintype "passive"))
      (node (ref "ARD_1") (pin "6") (pinfunction "6_6") (pintype "passive"))
      (node (ref "ARD_1") (pin "7") (pinfunction "7_7") (pintype "passive"))
      (node (ref "ARD_4") (pin "6") (pinfunction "6_6") (pintype "passive"))
      (node (ref "ARD_7") (pin "4") (pinfunction "4_4") (pintype "passive"))
      (node (ref "ARD_8") (pin "18") (pinfunction "18_18") (pintype "passive"))
      (node (ref "ARD_9") (pin "18") (pinfunction "18_18") (pintype "passive"))
      (node (ref "B1CC") (pin "2") (pinfunction "2_2") (pintype "passive"))
      (node (ref "B2CC") (pin "2") (pinfunction "2_2") (pintype "passive"))
      (node (ref "BATT_EXT") (pin "NEG") (pinfunction "NEG_NEG") (pintype "bidirectional"))
      (node (ref "C1") (pin "2") (pinfunction "2_2") (pintype "passive"))
      (node (ref "C1_TLM") (pin "15") (pinfunction "15_15") (pintype "passive"))
      (node (ref "C1_TLM") (pin "2") (pinfunction "2_2") (pintype "passive"))
      (node (ref "C2_PWR") (pin "2") (pinfunction "2_2") (pintype "passive"))
      (node (ref "C2_PWR") (pin "4") (pinfunction "4_4") (pintype "passive"))
      (node (ref "FLT_CMP_TMP_NEG") (pin "1") (pinfunction "1_1") (pintype "passive"))
      (node (ref "GPS") (pin "7") (pinfunction "7_7") (pintype "passive"))
      (node (ref "LCC") (pin "2") (pinfunction "2_2") (pintype "passive"))
      (node (ref "Q1") (pin "E") (pinfunction "E_E") (pintype "passive"))
      (node (ref "Q2") (pin "E") (pinfunction "E_E") (pintype "passive"))
      (node (ref "Q3") (pin "E") (pinfunction "E_E") (pintype "passive"))
      (node (ref "Q4") (pin "E") (pinfunction "E_E") (pintype "passive"))
      (node (ref "Q5") (pin "E") (pinfunction "E_E") (pintype "passive"))
      (node (ref "Q6") (pin "E") (pinfunction "E_E") (pintype "passive"))
      (node (ref "Q7") (pin "E") (pinfunction "E_E") (pintype "passive"))
      (node (ref "R12") (pin "1") (pinfunction "1_1") (pintype "passive"))
      (node (ref "R13") (pin "1") (pinfunction "1_1") (pintype "passive"))
      (node (ref "R15") (pin "1") (pinfunction "1_1") (pintype "passive"))
      (node (ref "R18") (pin "1") (pinfunction "1_1") (pintype "passive"))
      (node (ref "R19") (pin "1") (pinfunction "1_1") (pintype "passive"))
      (node (ref "R23") (pin "1") (pinfunction "1_1") (pintype "passive"))
      (node (ref "R25") (pin "1") (pinfunction "1_1") (pintype "passive"))
      (node (ref "R27") (pin "1") (pinfunction "1_1") (pintype "passive"))
      (node (ref "R3") (pin "1") (pinfunction "1_1") (pintype "passive"))
      (node (ref "R31") (pin "1") (pinfunction "1_1") (pintype "passive"))
      (node (ref "R33") (pin "1") (pinfunction "1_1") (pintype "passive"))
      (node (ref "R36") (pin "1") (pinfunction "1_1") (pintype "passive"))
      (node (ref "R38") (pin "1") (pinfunction "1_1") (pintype "passive"))
      (node (ref "R8") (pin "1") (pinfunction "1_1") (pintype "passive"))
      (node (ref "R9") (pin "1") (pinfunction "1_1") (pintype "passive"))
      (node (ref "RB1") (pin "6") (pinfunction "6_6") (pintype "passive"))
      (node (ref "RB2") (pin "1") (pinfunction "1_1") (pintype "passive"))
      (node (ref "RB2") (pin "8") (pinfunction "8_8") (pintype "passive"))
      (node (ref "SACC") (pin "2") (pinfunction "2_2") (pintype "passive"))
      (node (ref "U$2") (pin "P3_GND") (pinfunction "GND_P3_GND") (pintype "bidirectional"))
      (node (ref "U$4") (pin "GYRO_GND") (pinfunction "GYRO_GND_GYRO_GND") (pintype "bidirectional"))
      (node (ref "X1") (pin "2") (pinfunction "S_2") (pintype "passive"))
      (node (ref "X1") (pin "7") (pinfunction "S_7") (pintype "passive"))
      (node (ref "X2") (pin "10") (pinfunction "S_10") (pintype "passive"))
      (node (ref "X2") (pin "5") (pinfunction "S_5") (pintype "passive"))
      (node (ref "X2") (pin "8") (pinfunction "S_8") (pintype "passive"))
      (node (ref "X3") (pin "4") (pinfunction "4_4") (pintype "passive"))
    )
    (net (code "69") (name "GPS_EN") (class "Default")
      (node (ref "GPS") (pin "2") (pinfunction "2_2") (pintype "passive"))
    )
    (net (code "70") (name "GPS_FIX") (class "Default")
      (node (ref "GPS") (pin "4") (pinfunction "4_4") (pintype "passive"))
    )
    (net (code "71") (name "GPS_VBAT") (class "Default")
      (node (ref "GPS") (pin "3") (pinfunction "3_3") (pintype "passive"))
    )
    (net (code "72") (name "GYRO_PWR") (class "Default")
      (node (ref "ARD_8") (pin "5") (pinfunction "5_5") (pintype "passive"))
      (node (ref "U$4") (pin "GYRO_VCC") (pinfunction "GYRO_VCC_GYRO_VCC") (pintype "bidirectional"))
    )
    (net (code "73") (name "HEATER_1_PWR") (class "Default")
      (node (ref "C3_CMD") (pin "8") (pinfunction "8_8") (pintype "passive"))
      (node (ref "PO4") (pin "1") (pinfunction "P_1") (pintype "passive"))
      (node (ref "X1") (pin "9") (pinfunction "S_9") (pintype "passive"))
    )
    (net (code "74") (name "HEATER_1_PWR_RTN") (class "Default")
      (node (ref "C3_CMD") (pin "9") (pinfunction "9_9") (pintype "passive"))
      (node (ref "Q4") (pin "C") (pinfunction "C_C") (pintype "passive"))
      (node (ref "X1") (pin "10") (pinfunction "S_10") (pintype "passive"))
    )
    (net (code "75") (name "HEATER_2_PWR") (class "Default")
      (node (ref "C3_CMD") (pin "10") (pinfunction "10_10") (pintype "passive"))
      (node (ref "PO5") (pin "1") (pinfunction "P_1") (pintype "passive"))
      (node (ref "X1") (pin "4") (pinfunction "S_4") (pintype "passive"))
    )
    (net (code "76") (name "HEATER_2_PWR_RTN") (class "Default")
      (node (ref "C3_CMD") (pin "11") (pinfunction "11_11") (pintype "passive"))
      (node (ref "Q5") (pin "C") (pinfunction "C_C") (pintype "passive"))
      (node (ref "X1") (pin "5") (pinfunction "S_5") (pintype "passive"))
    )
    (net (code "77") (name "HEATER_CONTROL_1") (class "Default")
      (node (ref "ARD_7") (pin "10") (pinfunction "10_10") (pintype "passive"))
      (node (ref "R10") (pin "2") (pinfunction "2_2") (pintype "passive"))
    )
    (net (code "78") (name "HEATER_CONTROL_2") (class "Default")
      (node (ref "ARD_6") (pin "3") (pinfunction "3_3") (pintype "passive"))
      (node (ref "R11") (pin "2") (pinfunction "2_2") (pintype "passive"))
    )
    (net (code "79") (name "IOREF") (class "Default")
      (node (ref "ARD_1") (pin "2") (pinfunction "2_2") (pintype "passive"))
    )
    (net (code "80") (name "LI_ION") (class "Default")
      (node (ref "RB2") (pin "7") (pinfunction "7_7") (pintype "passive"))
    )
    (net (code "81") (name "LOAD_IN") (class "Default")
      (node (ref "LCC") (pin "6") (pinfunction "6_6") (pintype "passive"))
      (node (ref "X2") (pin "9") (pinfunction "S_9") (pintype "passive"))
    )
    (net (code "82") (name "LOAD_OUT") (class "Default")
      (node (ref "LCC") (pin "5") (pinfunction "5_5") (pintype "passive"))
      (node (ref "U$3") (pin "P1") (pinfunction "PIN_1_P1") (pintype "bidirectional"))
    )
    (net (code "83") (name "MISO") (class "Default")
      (node (ref "ARD_4") (pin "1") (pinfunction "1_1") (pintype "passive"))
      (node (ref "ARD_7") (pin "6") (pinfunction "6_6") (pintype "passive"))
    )
    (net (code "84") (name "MOSI") (class "Default")
      (node (ref "ARD_4") (pin "4") (pinfunction "4_4") (pintype "passive"))
      (node (ref "ARD_7") (pin "7") (pinfunction "7_7") (pintype "passive"))
    )
    (net (code "85") (name "NET_AV") (class "Default")
      (node (ref "RB2") (pin "5") (pinfunction "5_5") (pintype "passive"))
    )
    (net (code "86") (name "Net-(Q4-PadB)") (class "Default")
      (node (ref "Q4") (pin "B") (pinfunction "B_B") (pintype "passive"))
      (node (ref "R10") (pin "1") (pinfunction "1_1") (pintype "passive"))
      (node (ref "R12") (pin "2") (pinfunction "2_2") (pintype "passive"))
    )
    (net (code "87") (name "Net-(Q5-PadB)") (class "Default")
      (node (ref "Q5") (pin "B") (pinfunction "B_B") (pintype "passive"))
      (node (ref "R11") (pin "1") (pinfunction "1_1") (pintype "passive"))
      (node (ref "R13") (pin "2") (pinfunction "2_2") (pintype "passive"))
    )
    (net (code "88") (name "Net-(Q6-PadB)") (class "Default")
      (node (ref "Q6") (pin "B") (pinfunction "B_B") (pintype "passive"))
      (node (ref "R16") (pin "1") (pinfunction "1_1") (pintype "passive"))
      (node (ref "R18") (pin "2") (pinfunction "2_2") (pintype "passive"))
    )
    (net (code "89") (name "Net-(Q7-PadB)") (class "Default")
      (node (ref "Q7") (pin "B") (pinfunction "B_B") (pintype "passive"))
      (node (ref "R17") (pin "1") (pinfunction "1_1") (pintype "passive"))
      (node (ref "R19") (pin "2") (pinfunction "2_2") (pintype "passive"))
    )
    (net (code "90") (name "Net-(T1-B)") (class "Default")
      (node (ref "R1") (pin "1") (pinfunction "1_1") (pintype "passive"))
      (node (ref "R2") (pin "2") (pinfunction "2_2") (pintype "passive"))
      (node (ref "T1") (pin "2") (pinfunction "B_2") (pintype "passive"))
    )
    (net (code "91") (name "Net-(T1-E)") (class "Default")
      (node (ref "Q1") (pin "B") (pinfunction "B_B") (pintype "passive"))
      (node (ref "R2") (pin "1") (pinfunction "1_1") (pintype "passive"))
      (node (ref "R3") (pin "2") (pinfunction "2_2") (pintype "passive"))
      (node (ref "T1") (pin "3") (pinfunction "E_3") (pintype "passive"))
    )
    (net (code "92") (name "Net-(T2-B)") (class "Default")
      (node (ref "R4") (pin "1") (pinfunction "1_1") (pintype "passive"))
      (node (ref "R6") (pin "2") (pinfunction "2_2") (pintype "passive"))
      (node (ref "T2") (pin "2") (pinfunction "B_2") (pintype "passive"))
    )
    (net (code "93") (name "Net-(T2-E)") (class "Default")
      (node (ref "Q2") (pin "B") (pinfunction "B_B") (pintype "passive"))
      (node (ref "R6") (pin "1") (pinfunction "1_1") (pintype "passive"))
      (node (ref "R8") (pin "2") (pinfunction "2_2") (pintype "passive"))
      (node (ref "T2") (pin "3") (pinfunction "E_3") (pintype "passive"))
    )
    (net (code "94") (name "Net-(T3-B)") (class "Default")
      (node (ref "R5") (pin "1") (pinfunction "1_1") (pintype "passive"))
      (node (ref "R7") (pin "2") (pinfunction "2_2") (pintype "passive"))
      (node (ref "T3") (pin "2") (pinfunction "B_2") (pintype "passive"))
    )
    (net (code "95") (name "Net-(T3-E)") (class "Default")
      (node (ref "Q3") (pin "B") (pinfunction "B_B") (pintype "passive"))
      (node (ref "R7") (pin "1") (pinfunction "1_1") (pintype "passive"))
      (node (ref "R9") (pin "2") (pinfunction "2_2") (pintype "passive"))
      (node (ref "T3") (pin "3") (pinfunction "E_3") (pintype "passive"))
    )
    (net (code "96") (name "ON_OFF") (class "Default")
      (node (ref "RB2") (pin "6") (pinfunction "6_6") (pintype "passive"))
    )
    (net (code "97") (name "PYRO_1_PWR") (class "Default")
      (node (ref "C3_CMD") (pin "1") (pinfunction "1_1") (pintype "passive"))
      (node (ref "PO1") (pin "1") (pinfunction "P_1") (pintype "passive"))
    )
    (net (code "98") (name "PYRO_1_PWR_RTN") (class "Default")
      (node (ref "C3_CMD") (pin "2") (pinfunction "2_2") (pintype "passive"))
      (node (ref "Q1") (pin "C") (pinfunction "C_C") (pintype "passive"))
      (node (ref "T1") (pin "1") (pinfunction "C_1") (pintype "passive"))
    )
    (net (code "99") (name "PYRO_2_PWR") (class "Default")
      (node (ref "C3_CMD") (pin "3") (pinfunction "3_3") (pintype "passive"))
      (node (ref "PO2") (pin "1") (pinfunction "P_1") (pintype "passive"))
    )
    (net (code "100") (name "PYRO_2_PWR_RTN") (class "Default")
      (node (ref "C3_CMD") (pin "4") (pinfunction "4_4") (pintype "passive"))
      (node (ref "Q2") (pin "C") (pinfunction "C_C") (pintype "passive"))
      (node (ref "T2") (pin "1") (pinfunction "C_1") (pintype "passive"))
    )
    (net (code "101") (name "RESET") (class "Default")
      (node (ref "ARD_1") (pin "3") (pinfunction "3_3") (pintype "passive"))
      (node (ref "ARD_4") (pin "5") (pinfunction "5_5") (pintype "passive"))
      (node (ref "U$2") (pin "P1_RESET") (pinfunction "RESET_P1_RESET") (pintype "bidirectional"))
    )
    (net (code "102") (name "RI") (class "Default")
      (node (ref "RB2") (pin "4") (pinfunction "4_4") (pintype "passive"))
    )
    (net (code "103") (name "RTS") (class "Default")
      (node (ref "RB1") (pin "1") (pinfunction "1_1") (pintype "passive"))
    )
    (net (code "104") (name "RX0") (class "Default")
      (node (ref "ARD_6") (pin "8") (pinfunction "8_8") (pintype "passive"))
      (node (ref "X3") (pin "2") (pinfunction "2_2") (pintype "passive"))
    )
    (net (code "105") (name "RX1") (class "Default")
      (node (ref "ARD_5") (pin "6") (pinfunction "6_6") (pintype "passive"))
      (node (ref "GPS") (pin "5") (pinfunction "5_5") (pintype "passive"))
    )
    (net (code "106") (name "RX2") (class "Default")
      (node (ref "ARD_5") (pin "4") (pinfunction "4_4") (pintype "passive"))
    )
    (net (code "107") (name "RX3") (class "Default")
      (node (ref "ARD_5") (pin "2") (pinfunction "2_2") (pintype "passive"))
      (node (ref "RB1") (pin "2") (pinfunction "2_2") (pintype "passive"))
    )
    (net (code "108") (name "SCK") (class "Default")
      (node (ref "ARD_4") (pin "3") (pinfunction "3_3") (pintype "passive"))
      (node (ref "ARD_7") (pin "5") (pinfunction "5_5") (pintype "passive"))
    )
    (net (code "109") (name "SCL") (class "Default")
      (node (ref "ARD_5") (pin "8") (pinfunction "8_8") (pintype "passive"))
      (node (ref "B1CC") (pin "3") (pinfunction "3_3") (pintype "passive"))
      (node (ref "B2CC") (pin "3") (pinfunction "3_3") (pintype "passive"))
      (node (ref "LCC") (pin "3") (pinfunction "3_3") (pintype "passive"))
      (node (ref "SACC") (pin "3") (pinfunction "3_3") (pintype "passive"))
      (node (ref "U$4") (pin "GYRO_SCL") (pinfunction "GYRO_SCL_GYRO_SCL") (pintype "bidirectional"))
    )
    (net (code "110") (name "SCL1") (class "Default")
      (node (ref "ARD_7") (pin "1") (pinfunction "1_1") (pintype "passive"))
      (node (ref "C1_TLM") (pin "6") (pinfunction "6_6") (pintype "passive"))
    )
    (net (code "111") (name "SDA") (class "Default")
      (node (ref "ARD_5") (pin "7") (pinfunction "7_7") (pintype "passive"))
      (node (ref "B1CC") (pin "4") (pinfunction "4_4") (pintype "passive"))
      (node (ref "B2CC") (pin "4") (pinfunction "4_4") (pintype "passive"))
      (node (ref "LCC") (pin "4") (pinfunction "4_4") (pintype "passive"))
      (node (ref "SACC") (pin "4") (pinfunction "4_4") (pintype "passive"))
      (node (ref "U$4") (pin "GYRO_SDA") (pinfunction "GYRO_SDA_GYRO_SDA") (pintype "bidirectional"))
    )
    (net (code "112") (name "SDA1") (class "Default")
      (node (ref "ARD_7") (pin "2") (pinfunction "2_2") (pintype "passive"))
      (node (ref "C1_TLM") (pin "5") (pinfunction "5_5") (pintype "passive"))
    )
    (net (code "113") (name "SPARE_1_PWR") (class "Default")
      (node (ref "C3_CMD") (pin "12") (pinfunction "12_12") (pintype "passive"))
      (node (ref "PO6") (pin "1") (pinfunction "P_1") (pintype "passive"))
      (node (ref "SPRL1") (pin "1") (pinfunction "S_1") (pintype "passive"))
    )
    (net (code "114") (name "SPARE_1_PWR_RTN") (class "Default")
      (node (ref "C3_CMD") (pin "13") (pinfunction "13_13") (pintype "passive"))
      (node (ref "Q6") (pin "C") (pinfunction "C_C") (pintype "passive"))
    )
    (net (code "115") (name "SPARE_HIGH_1_CONTROL") (class "Default")
      (node (ref "ARD_9") (pin "2") (pinfunction "2_2") (pintype "passive"))
      (node (ref "R5") (pin "2") (pinfunction "2_2") (pintype "passive"))
    )
    (net (code "116") (name "SPARE_HIGH_1_PWR") (class "Default")
      (node (ref "C3_CMD") (pin "5") (pinfunction "5_5") (pintype "passive"))
      (node (ref "PO3") (pin "1") (pinfunction "P_1") (pintype "passive"))
      (node (ref "SPRH1") (pin "1") (pinfunction "S_1") (pintype "passive"))
    )
    (net (code "117") (name "SPARE_HIGH_1_PWR_RTN") (class "Default")
      (node (ref "C3_CMD") (pin "6") (pinfunction "6_6") (pintype "passive"))
      (node (ref "Q3") (pin "C") (pinfunction "C_C") (pintype "passive"))
      (node (ref "T3") (pin "1") (pinfunction "C_1") (pintype "passive"))
    )
    (net (code "118") (name "SPARE_LOW_1_CONTROL") (class "Default")
      (node (ref "ARD_9") (pin "3") (pinfunction "3_3") (pintype "passive"))
      (node (ref "R16") (pin "2") (pinfunction "2_2") (pintype "passive"))
    )
    (net (code "119") (name "S{slash}A_PWR_IN") (class "Default")
      (node (ref "C2_PWR") (pin "10") (pinfunction "10_10") (pintype "passive"))
      (node (ref "C2_PWR") (pin "6") (pinfunction "6_6") (pintype "passive"))
      (node (ref "C2_PWR") (pin "8") (pinfunction "8_8") (pintype "passive"))
      (node (ref "SACC") (pin "6") (pinfunction "6_6") (pintype "passive"))
      (node (ref "U$3") (pin "P2") (pinfunction "PIN_2_P2") (pintype "bidirectional"))
    )
    (net (code "120") (name "S{slash}A_PWR_OUT") (class "Default")
      (node (ref "SACC") (pin "5") (pinfunction "5_5") (pintype "passive"))
      (node (ref "U$3") (pin "P2A") (pinfunction "PIN_2A_P2A") (pintype "bidirectional"))
      (node (ref "X2") (pin "1") (pinfunction "S_1") (pintype "passive"))
    )
    (net (code "121") (name "S{slash}A_PWR_RTN") (class "Default")
      (node (ref "C2_PWR") (pin "11") (pinfunction "11_11") (pintype "passive"))
      (node (ref "C2_PWR") (pin "7") (pinfunction "7_7") (pintype "passive"))
      (node (ref "C2_PWR") (pin "9") (pinfunction "9_9") (pintype "passive"))
      (node (ref "X2") (pin "2") (pinfunction "S_2") (pintype "passive"))
    )
    (net (code "122") (name "TEMP_EXT_1") (class "Default")
      (node (ref "ARD_2") (pin "8") (pinfunction "8_8") (pintype "passive"))
      (node (ref "C1_TLM") (pin "1") (pinfunction "1_1") (pintype "passive"))
      (node (ref "R22") (pin "1") (pinfunction "1_1") (pintype "passive"))
      (node (ref "R23") (pin "2") (pinfunction "2_2") (pintype "passive"))
    )
    (net (code "123") (name "TEMP_EXT_2") (class "Default")
      (node (ref "ARD_2") (pin "6") (pinfunction "6_6") (pintype "passive"))
      (node (ref "C1_TLM") (pin "3") (pinfunction "3_3") (pintype "passive"))
      (node (ref "R24") (pin "1") (pinfunction "1_1") (pintype "passive"))
      (node (ref "R25") (pin "2") (pinfunction "2_2") (pintype "passive"))
    )
    (net (code "124") (name "TX0") (class "Default")
      (node (ref "ARD_6") (pin "7") (pinfunction "7_7") (pintype "passive"))
      (node (ref "X3") (pin "3") (pinfunction "3_3") (pintype "passive"))
    )
    (net (code "125") (name "TX1") (class "Default")
      (node (ref "ARD_5") (pin "5") (pinfunction "5_5") (pintype "passive"))
      (node (ref "GPS") (pin "6") (pinfunction "6_6") (pintype "passive"))
    )
    (net (code "126") (name "TX2") (class "Default")
      (node (ref "ARD_5") (pin "3") (pinfunction "3_3") (pintype "passive"))
    )
    (net (code "127") (name "TX3") (class "Default")
      (node (ref "ARD_5") (pin "1") (pinfunction "1_1") (pintype "passive"))
      (node (ref "RB1") (pin "3") (pinfunction "3_3") (pintype "passive"))
    )
    (net (code "128") (name "UNKNOWN") (class "Default")
      (node (ref "ARD_1") (pin "1") (pinfunction "1_1") (pintype "passive"))
    )
    (net (code "129") (name "VCC_RB") (class "Default")
      (node (ref "RB1") (pin "4") (pinfunction "4_4") (pintype "passive"))
    )
    (net (code "130") (name "VIN") (class "Default")
      (node (ref "ARD_1") (pin "8") (pinfunction "8_8") (pintype "passive"))
      (node (ref "GPS") (pin "8") (pinfunction "8_8") (pintype "passive"))
      (node (ref "PVIN1") (pin "1") (pinfunction "P_1") (pintype "passive"))
      (node (ref "PVIN2") (pin "1") (pinfunction "P_1") (pintype "passive"))
      (node (ref "PVIN3") (pin "1") (pinfunction "P_1") (pintype "passive"))
      (node (ref "PVIN4") (pin "1") (pinfunction "P_1") (pintype "passive"))
      (node (ref "PVIN5") (pin "1") (pinfunction "P_1") (pintype "passive"))
      (node (ref "PVIN6") (pin "1") (pinfunction "P_1") (pintype "passive"))
      (node (ref "PVIN7") (pin "1") (pinfunction "P_1") (pintype "passive"))
      (node (ref "R14") (pin "2") (pinfunction "2_2") (pintype "passive"))
      (node (ref "U$3") (pin "P1A") (pinfunction "PIN_1A_P1A") (pintype "bidirectional"))
    )
    (net (code "131") (name "VIN_VOLTAGE_TLM") (class "Default")
      (node (ref "ARD_2") (pin "4") (pinfunction "4_4") (pintype "passive"))
      (node (ref "C1") (pin "1") (pinfunction "1_1") (pintype "passive"))
      (node (ref "R14") (pin "1") (pinfunction "1_1") (pintype "passive"))
      (node (ref "R15") (pin "2") (pinfunction "2_2") (pintype "passive"))
    )
    (net (code "132") (name "unconnected-(ALT-Pad8)") (class "Default")
      (node (ref "ALT") (pin "8") (pinfunction "8_8") (pintype "passive"))
    )
    (net (code "133") (name "unconnected-(C2_PWR-Pad5)") (class "Default")
      (node (ref "C2_PWR") (pin "5") (pinfunction "5_5") (pintype "passive"))
    )
    (net (code "134") (name "unconnected-(C2_PWR-Pad12)") (class "Default")
      (node (ref "C2_PWR") (pin "12") (pinfunction "12_12") (pintype "passive"))
    )
    (net (code "135") (name "unconnected-(C2_PWR-Pad13)") (class "Default")
      (node (ref "C2_PWR") (pin "13") (pinfunction "13_13") (pintype "passive"))
    )
    (net (code "136") (name "unconnected-(C2_PWR-Pad14)") (class "Default")
      (node (ref "C2_PWR") (pin "14") (pinfunction "14_14") (pintype "passive"))
    )
    (net (code "137") (name "unconnected-(C2_PWR-Pad15)") (class "Default")
      (node (ref "C2_PWR") (pin "15") (pinfunction "15_15") (pintype "passive"))
    )
    (net (code "138") (name "unconnected-(C3_CMD-Pad7)") (class "Default")
      (node (ref "C3_CMD") (pin "7") (pinfunction "7_7") (pintype "passive"))
    )
    (net (code "139") (name "unconnected-(IC1-+IN-Pad3)") (class "Default")
      (node (ref "IC1") (pin "3") (pinfunction "+IN_3") (pintype "input"))
    )
    (net (code "140") (name "unconnected-(IC1--IN-Pad2)") (class "Default")
      (node (ref "IC1") (pin "2") (pinfunction "-IN_2") (pintype "input"))
    )
    (net (code "141") (name "unconnected-(IC1-BYPASS-Pad7)") (class "Default")
      (node (ref "IC1") (pin "7") (pinfunction "BYPASS_7") (pintype "passive"))
    )
    (net (code "142") (name "unconnected-(IC1-GAIN-Pad1)") (class "Default")
      (node (ref "IC1") (pin "1") (pinfunction "GAIN_1") (pintype "passive"))
    )
    (net (code "143") (name "unconnected-(U$2-NC1-PadP2_NC)") (class "Default")
      (node (ref "U$2") (pin "P2_NC") (pinfunction "NC1_P2_NC") (pintype "bidirectional"))
    )
    (net (code "144") (name "unconnected-(U$2-NC2-PadP4_NC)") (class "Default")
      (node (ref "U$2") (pin "P4_NC") (pinfunction "NC2_P4_NC") (pintype "bidirectional"))
    )
  )
)
